# TurnoutController.net
KiCad netlist of a schematic drawn in EAGLE
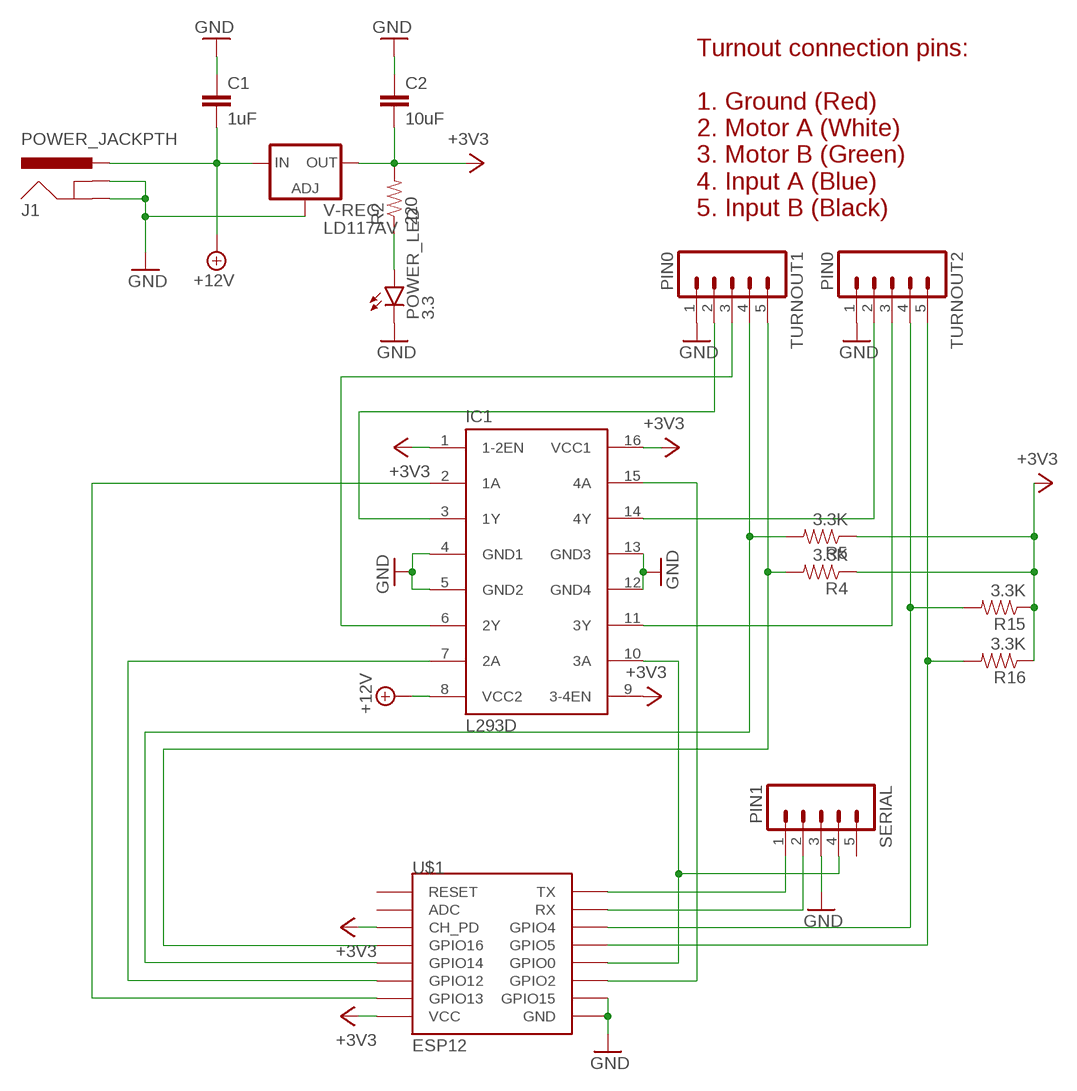
[diagram p0: schematic, sheet 1]

(export (version "E")
  (design (tool "Eeschema 10.0.6"))
  (components
    (comp (ref "C1")
      (value "1uF")
      (footprint "eagle-import:CAP-PTH-SMALL")
      (libsource (lib "eagle-import") (part "CAPPTH"))
    )
    (comp (ref "C2")
      (value "10uF")
      (footprint "eagle-import:CAP-PTH-SMALL")
      (libsource (lib "eagle-import") (part "CAPPTH"))
    )
    (comp (ref "IC1")
      (value "L293D")
      (footprint "eagle-import:DIL16")
      (libsource (lib "eagle-import") (part "L293D"))
    )
    (comp (ref "J1")
      (value "POWER_JACKPTH")
      (footprint "eagle-import:POWER_JACK_PTH")
      (libsource (lib "eagle-import") (part "POWER_JACKPTH"))
    )
    (comp (ref "POWER_LED")
      (value "3.3")
      (footprint "eagle-import:LED5MM")
      (libsource (lib "eagle-import") (part "LED5MM"))
    )
    (comp (ref "R2")
      (value "220")
      (footprint "eagle-import:AXIAL-0.4")
      (libsource (lib "eagle-import") (part "RESISTORPTH-1/4W"))
    )
    (comp (ref "R4")
      (value "3.3K")
      (footprint "eagle-import:AXIAL-0.4")
      (libsource (lib "eagle-import") (part "RESISTORPTH-1/4W"))
    )
    (comp (ref "R5")
      (value "3.3K")
      (footprint "eagle-import:AXIAL-0.4")
      (libsource (lib "eagle-import") (part "RESISTORPTH-1/4W"))
    )
    (comp (ref "R15")
      (value "3.3K")
      (footprint "eagle-import:AXIAL-0.4")
      (libsource (lib "eagle-import") (part "RESISTORPTH-1/4W"))
    )
    (comp (ref "R16")
      (value "3.3K")
      (footprint "eagle-import:AXIAL-0.4")
      (libsource (lib "eagle-import") (part "RESISTORPTH-1/4W"))
    )
    (comp (ref "SERIAL")
      (value "PIN1")
      (footprint "eagle-import:05P")
      (libsource (lib "eagle-import") (part "M05"))
    )
    (comp (ref "TURNOUT1")
      (value "PIN0")
      (footprint "eagle-import:05P")
      (libsource (lib "eagle-import") (part "M05"))
    )
    (comp (ref "TURNOUT2")
      (value "PIN0")
      (footprint "eagle-import:05P")
      (libsource (lib "eagle-import") (part "M05"))
    )
    (comp (ref "U$1")
      (value "ESP12")
      (footprint "eagle-import:ESP12")
      (libsource (lib "eagle-import") (part "ESP12"))
    )
    (comp (ref "V-REG")
      (value "LD117AV")
      (footprint "eagle-import:TO220L1")
      (libsource (lib "eagle-import") (part "LD117A?V"))
    )
  )
  (nets
    (net (code "1") (name "+3V3") (class "Default")
      (node (ref "C2") (pin "2") (pinfunction "2_2") (pintype "passive"))
      (node (ref "IC1") (pin "1") (pinfunction "1-2EN_1") (pintype "input"))
      (node (ref "IC1") (pin "16") (pinfunction "VCC1_16") (pintype "power_in"))
      (node (ref "IC1") (pin "9") (pinfunction "3-4EN_9") (pintype "input"))
      (node (ref "R15") (pin "P$1") (pinfunction "1_P$1") (pintype "passive"))
      (node (ref "R16") (pin "P$1") (pinfunction "1_P$1") (pintype "passive"))
      (node (ref "R2") (pin "P$2") (pinfunction "2_P$2") (pintype "passive"))
      (node (ref "R4") (pin "P$1") (pinfunction "1_P$1") (pintype "passive"))
      (node (ref "R5") (pin "P$1") (pinfunction "1_P$1") (pintype "passive"))
      (node (ref "U$1") (pin "CH_PD") (pinfunction "CH_PD_CH_PD") (pintype "bidirectional"))
      (node (ref "U$1") (pin "VCC") (pinfunction "VCC_VCC") (pintype "bidirectional"))
      (node (ref "V-REG") (pin "2") (pinfunction "OUT_2") (pintype "passive"))
    )
    (net (code "2") (name "+12V") (class "Default")
      (node (ref "C1") (pin "2") (pinfunction "2_2") (pintype "passive"))
      (node (ref "IC1") (pin "8") (pinfunction "VCC2_8") (pintype "power_in"))
      (node (ref "J1") (pin "PWR") (pinfunction "PWR_PWR") (pintype "bidirectional"))
      (node (ref "V-REG") (pin "3") (pinfunction "IN_3") (pintype "input"))
    )
    (net (code "3") (name "GND") (class "Default")
      (node (ref "C1") (pin "1") (pinfunction "1_1") (pintype "passive"))
      (node (ref "C2") (pin "1") (pinfunction "1_1") (pintype "passive"))
      (node (ref "IC1") (pin "12") (pinfunction "GND4_12") (pintype "power_in"))
      (node (ref "IC1") (pin "13") (pinfunction "GND3_13") (pintype "power_in"))
      (node (ref "IC1") (pin "4") (pinfunction "GND1_4") (pintype "power_in"))
      (node (ref "IC1") (pin "5") (pinfunction "GND2_5") (pintype "power_in"))
      (node (ref "J1") (pin "GND") (pinfunction "GND_GND") (pintype "bidirectional"))
      (node (ref "J1") (pin "GNDBREAK") (pinfunction "GNDBREAK_GNDBREAK") (pintype "bidirectional"))
      (node (ref "POWER_LED") (pin "K") (pinfunction "C_K") (pintype "passive"))
      (node (ref "SERIAL") (pin "3") (pinfunction "3_3") (pintype "passive"))
      (node (ref "TURNOUT1") (pin "1") (pinfunction "1_1") (pintype "passive"))
      (node (ref "TURNOUT2") (pin "1") (pinfunction "1_1") (pintype "passive"))
      (node (ref "U$1") (pin "GND") (pinfunction "GND_GND") (pintype "bidirectional"))
      (node (ref "U$1") (pin "GPIO15") (pinfunction "GPIO15_GPIO15") (pintype "bidirectional"))
      (node (ref "V-REG") (pin "1") (pinfunction "ADJ_1") (pintype "input"))
    )
    (net (code "4") (name "Net-(IC1-1A)") (class "Default")
      (node (ref "IC1") (pin "2") (pinfunction "1A_2") (pintype "input"))
      (node (ref "U$1") (pin "GPIO13") (pinfunction "GPIO13_GPIO13") (pintype "bidirectional"))
    )
    (net (code "5") (name "Net-(IC1-1Y)") (class "Default")
      (node (ref "IC1") (pin "3") (pinfunction "1Y_3") (pintype "output"))
      (node (ref "TURNOUT1") (pin "2") (pinfunction "2_2") (pintype "passive"))
    )
    (net (code "6") (name "Net-(IC1-2A)") (class "Default")
      (node (ref "IC1") (pin "7") (pinfunction "2A_7") (pintype "input"))
      (node (ref "U$1") (pin "GPIO12") (pinfunction "GPIO12_GPIO12") (pintype "bidirectional"))
    )
    (net (code "7") (name "Net-(IC1-2Y)") (class "Default")
      (node (ref "IC1") (pin "6") (pinfunction "2Y_6") (pintype "output"))
      (node (ref "TURNOUT1") (pin "3") (pinfunction "3_3") (pintype "passive"))
    )
    (net (code "8") (name "Net-(IC1-3A)") (class "Default")
      (node (ref "IC1") (pin "10") (pinfunction "3A_10") (pintype "input"))
      (node (ref "SERIAL") (pin "4") (pinfunction "4_4") (pintype "passive"))
      (node (ref "U$1") (pin "GPIO0") (pinfunction "GPIO0_GPIO0") (pintype "bidirectional"))
    )
    (net (code "9") (name "Net-(IC1-3Y)") (class "Default")
      (node (ref "IC1") (pin "11") (pinfunction "3Y_11") (pintype "output"))
      (node (ref "TURNOUT2") (pin "3") (pinfunction "3_3") (pintype "passive"))
    )
    (net (code "10") (name "Net-(IC1-4A)") (class "Default")
      (node (ref "IC1") (pin "15") (pinfunction "4A_15") (pintype "input"))
      (node (ref "U$1") (pin "GPIO2") (pinfunction "GPIO2_GPIO2") (pintype "bidirectional"))
    )
    (net (code "11") (name "Net-(IC1-4Y)") (class "Default")
      (node (ref "IC1") (pin "14") (pinfunction "4Y_14") (pintype "output"))
      (node (ref "TURNOUT2") (pin "2") (pinfunction "2_2") (pintype "passive"))
    )
    (net (code "12") (name "Net-(R2-1)") (class "Default")
      (node (ref "POWER_LED") (pin "A") (pinfunction "A_A") (pintype "passive"))
      (node (ref "R2") (pin "P$1") (pinfunction "1_P$1") (pintype "passive"))
    )
    (net (code "13") (name "Net-(R4-2)") (class "Default")
      (node (ref "R4") (pin "P$2") (pinfunction "2_P$2") (pintype "passive"))
      (node (ref "TURNOUT1") (pin "5") (pinfunction "5_5") (pintype "passive"))
      (node (ref "U$1") (pin "GPIO16") (pinfunction "GPIO16_GPIO16") (pintype "bidirectional"))
    )
    (net (code "14") (name "Net-(R5-2)") (class "Default")
      (node (ref "R5") (pin "P$2") (pinfunction "2_P$2") (pintype "passive"))
      (node (ref "TURNOUT1") (pin "4") (pinfunction "4_4") (pintype "passive"))
      (node (ref "U$1") (pin "GPIO14") (pinfunction "GPIO14_GPIO14") (pintype "bidirectional"))
    )
    (net (code "15") (name "Net-(R15-2)") (class "Default")
      (node (ref "R15") (pin "P$2") (pinfunction "2_P$2") (pintype "passive"))
      (node (ref "TURNOUT2") (pin "4") (pinfunction "4_4") (pintype "passive"))
      (node (ref "U$1") (pin "GPIO4") (pinfunction "GPIO4_GPIO4") (pintype "bidirectional"))
    )
    (net (code "16") (name "Net-(R16-2)") (class "Default")
      (node (ref "R16") (pin "P$2") (pinfunction "2_P$2") (pintype "passive"))
      (node (ref "TURNOUT2") (pin "5") (pinfunction "5_5") (pintype "passive"))
      (node (ref "U$1") (pin "GPIO5") (pinfunction "GPIO5_GPIO5") (pintype "bidirectional"))
    )
    (net (code "17") (name "Net-(SERIAL-Pad1)") (class "Default")
      (node (ref "SERIAL") (pin "1") (pinfunction "1_1") (pintype "passive"))
      (node (ref "U$1") (pin "TX") (pinfunction "TX_TX") (pintype "bidirectional"))
    )
    (net (code "18") (name "Net-(SERIAL-Pad2)") (class "Default")
      (node (ref "SERIAL") (pin "2") (pinfunction "2_2") (pintype "passive"))
      (node (ref "U$1") (pin "RX") (pinfunction "RX_RX") (pintype "bidirectional"))
    )
    (net (code "19") (name "unconnected-(SERIAL-Pad5)") (class "Default")
      (node (ref "SERIAL") (pin "5") (pinfunction "5_5") (pintype "passive"))
    )
    (net (code "20") (name "unconnected-(U$1-PadADC)") (class "Default")
      (node (ref "U$1") (pin "ADC") (pinfunction "ADC_ADC") (pintype "bidirectional"))
    )
    (net (code "21") (name "unconnected-(U$1-PadRESET)") (class "Default")
      (node (ref "U$1") (pin "RESET") (pinfunction "RESET_RESET") (pintype "bidirectional"))
    )
  )
)
